# circuit_EDA.net
KiCad netlist of a schematic drawn in EasyEDA
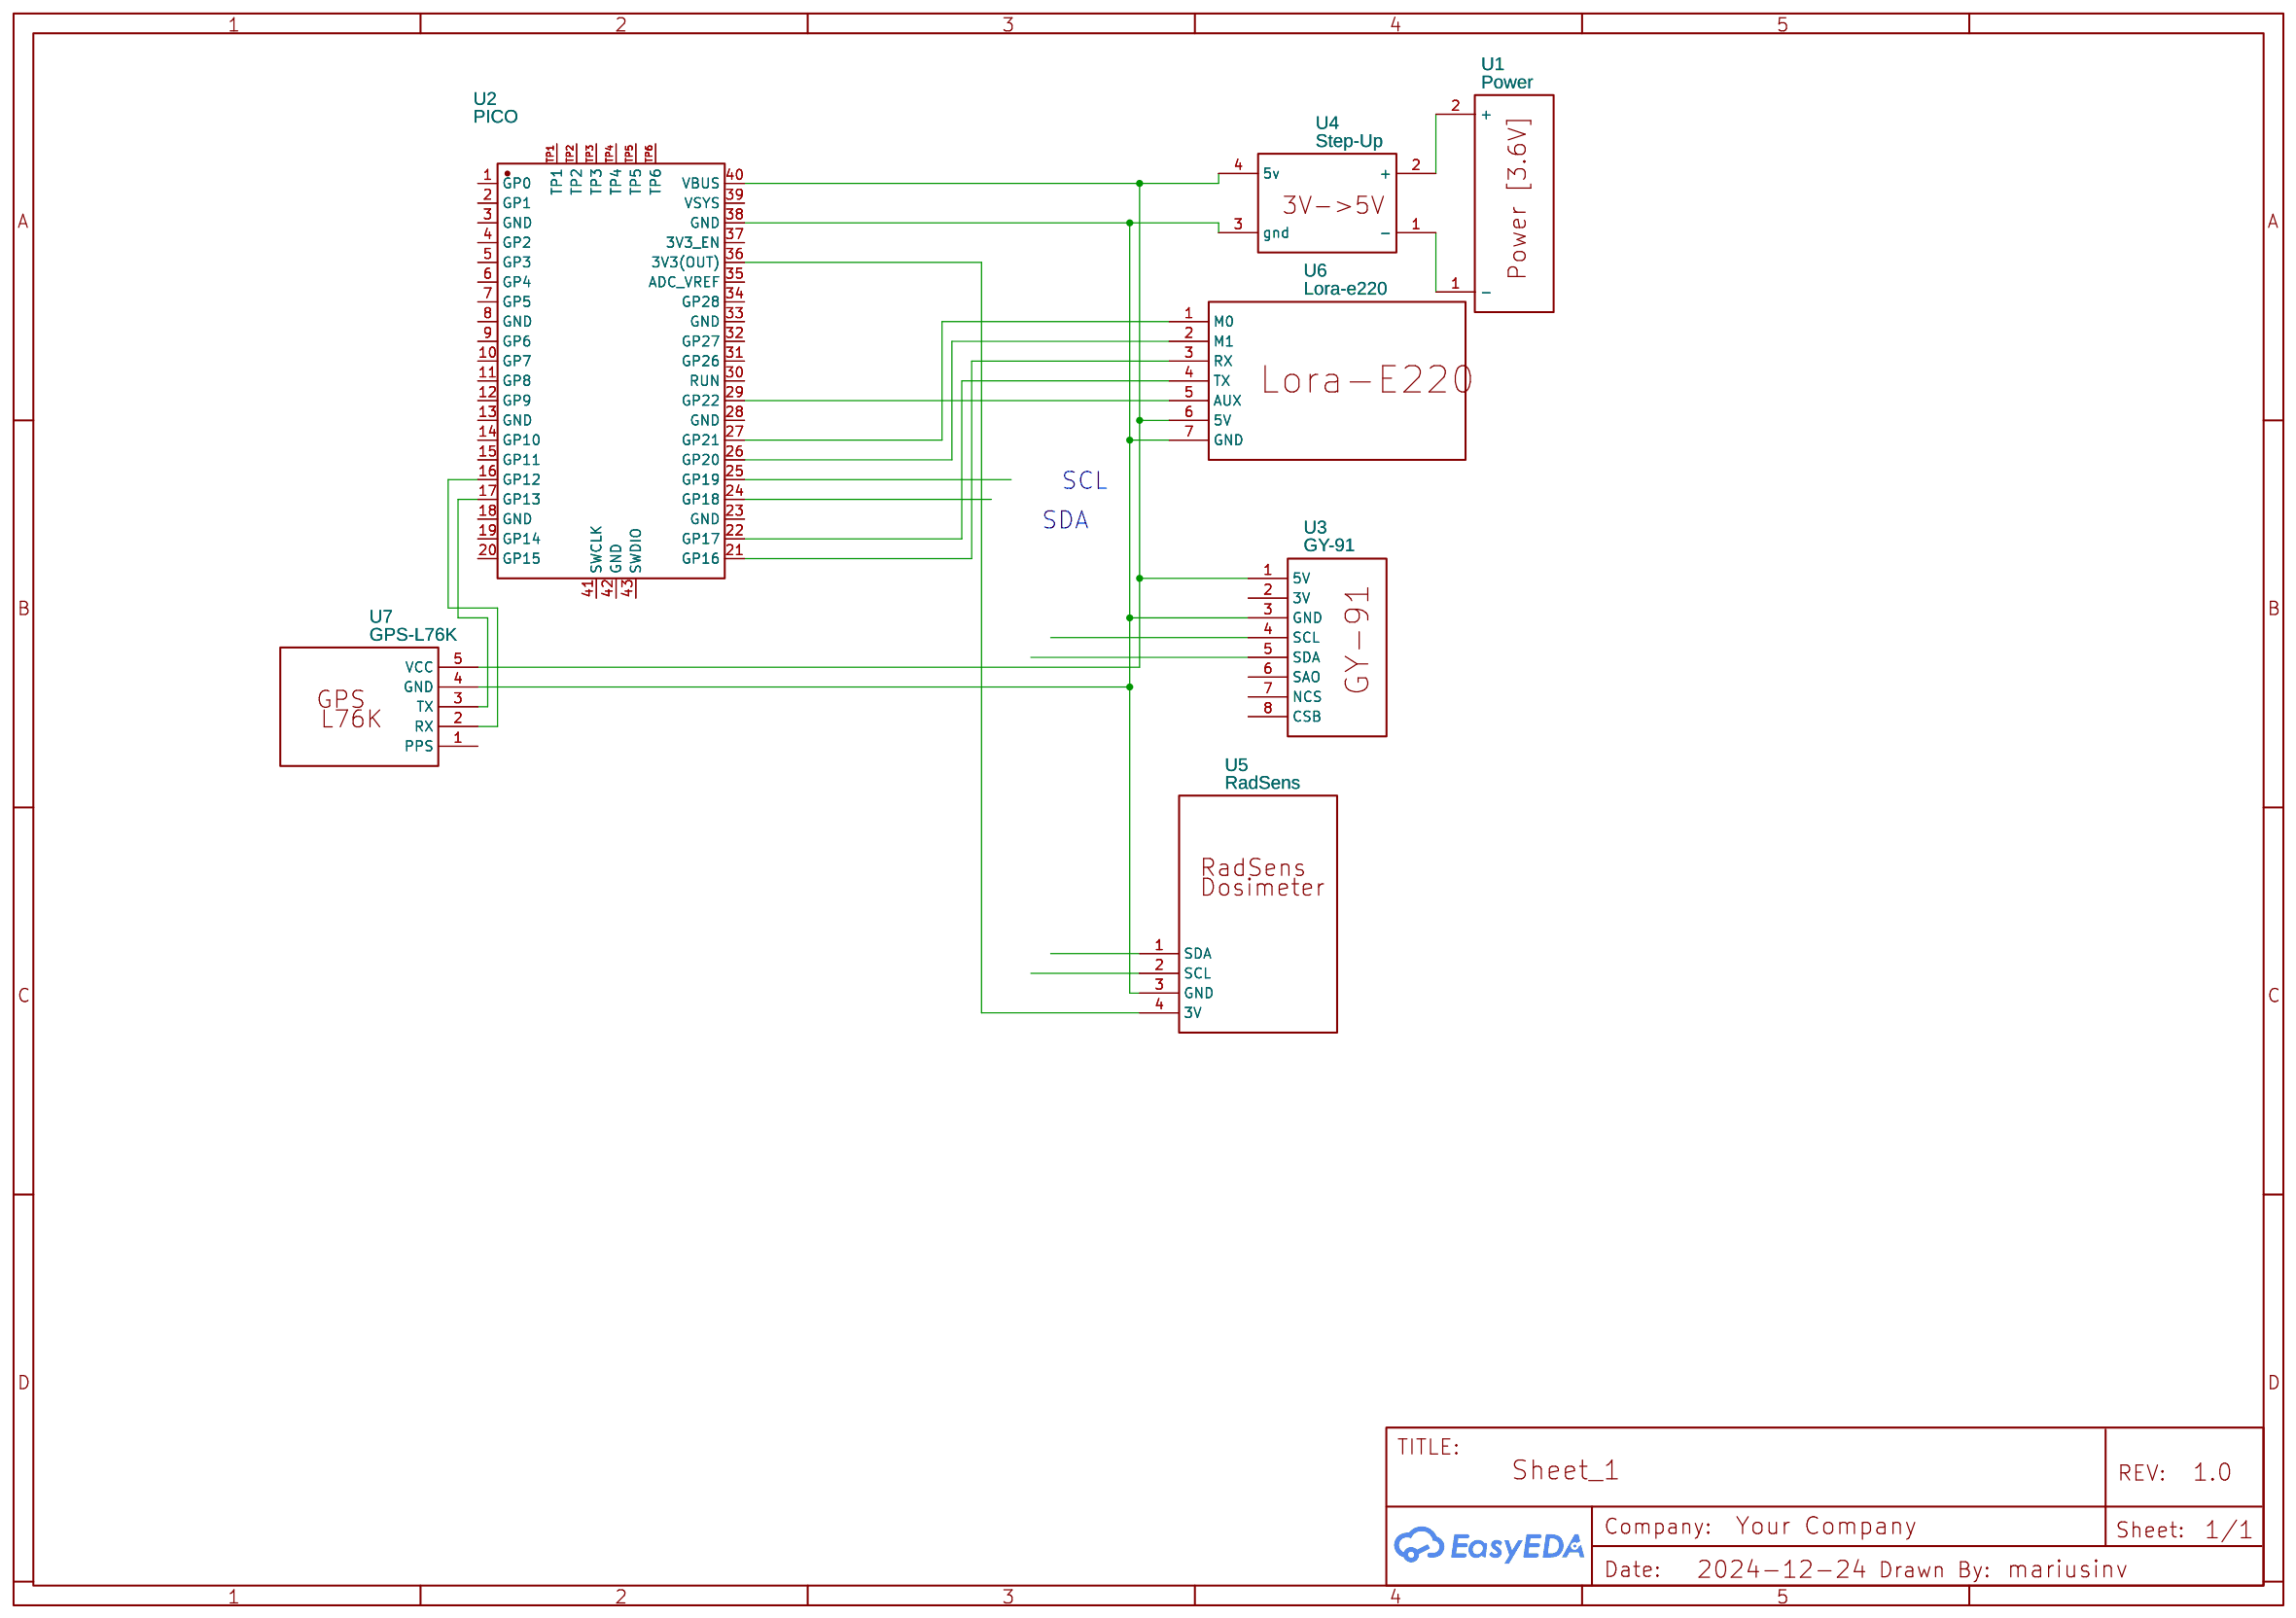
[diagram p0: schematic sheet]

(export (version "E")
  (design (tool "Eeschema 10.0.6"))
  (components
    (comp (ref "U1") (value "Power") (libsource (lib "") (part "Power")))
    (comp (ref "U2")
      (value "PICO")
      (fields (field (name "Manufacturer") "Raspberry Pi(树莓派)"))
      (libsource (lib "") (part "PICO"))
    )
    (comp (ref "U3") (value "GY-91") (libsource (lib "") (part "GY-91")))
    (comp (ref "U4") (value "Step-Up") (libsource (lib "") (part "Step-Up")))
    (comp (ref "U5") (value "RadSens") (libsource (lib "") (part "RadSens")))
    (comp (ref "U6") (value "Lora-e220") (libsource (lib "") (part "Lora-e220")))
    (comp (ref "U7") (value "GPS-L76K") (libsource (lib "") (part "GPS-L76K")))
  )
  (nets
    (net (code "1") (name "Net-(U1-+)") (class "Default")
      (node (ref "U1") (pin "2") (pinfunction "+_2") (pintype "unspecified"))
      (node (ref "U4") (pin "2") (pinfunction "+_2") (pintype "unspecified"))
    )
    (net (code "2") (name "Net-(U1--)") (class "Default")
      (node (ref "U1") (pin "1") (pinfunction "-_1") (pintype "unspecified"))
      (node (ref "U4") (pin "1") (pinfunction "-_1") (pintype "unspecified"))
    )
    (net (code "3") (name "Net-(U2-3V3(OUT))") (class "Default")
      (node (ref "U2") (pin "36") (pinfunction "3V3(OUT)_36") (pintype "unspecified"))
      (node (ref "U5") (pin "4") (pinfunction "3V_4") (pintype "unspecified"))
    )
    (net (code "4") (name "Net-(U2-GP12)") (class "Default")
      (node (ref "U2") (pin "16") (pinfunction "GP12_16") (pintype "unspecified"))
      (node (ref "U7") (pin "2") (pinfunction "RX_2") (pintype "unspecified"))
    )
    (net (code "5") (name "Net-(U2-GP13)") (class "Default")
      (node (ref "U2") (pin "17") (pinfunction "GP13_17") (pintype "unspecified"))
      (node (ref "U7") (pin "3") (pinfunction "TX_3") (pintype "unspecified"))
    )
    (net (code "6") (name "Net-(U2-GP16)") (class "Default")
      (node (ref "U2") (pin "21") (pinfunction "GP16_21") (pintype "unspecified"))
      (node (ref "U6") (pin "3") (pinfunction "RX_3") (pintype "unspecified"))
    )
    (net (code "7") (name "Net-(U2-GP17)") (class "Default")
      (node (ref "U2") (pin "22") (pinfunction "GP17_22") (pintype "unspecified"))
      (node (ref "U6") (pin "4") (pinfunction "TX_4") (pintype "unspecified"))
    )
    (net (code "8") (name "Net-(U2-GP20)") (class "Default")
      (node (ref "U2") (pin "26") (pinfunction "GP20_26") (pintype "unspecified"))
      (node (ref "U6") (pin "2") (pinfunction "M1_2") (pintype "unspecified"))
    )
    (net (code "9") (name "Net-(U2-GP21)") (class "Default")
      (node (ref "U2") (pin "27") (pinfunction "GP21_27") (pintype "unspecified"))
      (node (ref "U6") (pin "1") (pinfunction "M0_1") (pintype "unspecified"))
    )
    (net (code "10") (name "Net-(U2-GP22)") (class "Default")
      (node (ref "U2") (pin "29") (pinfunction "GP22_29") (pintype "unspecified"))
      (node (ref "U6") (pin "5") (pinfunction "AUX_5") (pintype "unspecified"))
    )
    (net (code "11") (name "Net-(U2-VBUS)") (class "Default")
      (node (ref "U2") (pin "40") (pinfunction "VBUS_40") (pintype "unspecified"))
      (node (ref "U3") (pin "1") (pinfunction "5V_1") (pintype "unspecified"))
      (node (ref "U4") (pin "4") (pinfunction "5v_4") (pintype "unspecified"))
      (node (ref "U6") (pin "6") (pinfunction "5V_6") (pintype "unspecified"))
      (node (ref "U7") (pin "5") (pinfunction "VCC_5") (pintype "unspecified"))
    )
    (net (code "12") (name "Net-(U3-GND)") (class "Default")
      (node (ref "U2") (pin "38") (pinfunction "GND_38") (pintype "unspecified"))
      (node (ref "U3") (pin "3") (pinfunction "GND_3") (pintype "unspecified"))
      (node (ref "U4") (pin "3") (pinfunction "gnd_3") (pintype "unspecified"))
      (node (ref "U5") (pin "3") (pinfunction "GND_3") (pintype "unspecified"))
      (node (ref "U6") (pin "7") (pinfunction "GND_7") (pintype "unspecified"))
      (node (ref "U7") (pin "4") (pinfunction "GND_4") (pintype "unspecified"))
    )
    (net (code "13") (name "unconnected-(U2-3V3_EN-Pad37)") (class "Default")
      (node (ref "U2") (pin "37") (pinfunction "3V3_EN_37") (pintype "unspecified"))
    )
    (net (code "14") (name "unconnected-(U2-ADC_VREF-Pad35)") (class "Default")
      (node (ref "U2") (pin "35") (pinfunction "ADC_VREF_35") (pintype "unspecified"))
    )
    (net (code "15") (name "unconnected-(U2-GND-Pad3)") (class "Default")
      (node (ref "U2") (pin "3") (pinfunction "GND_3") (pintype "unspecified"))
    )
    (net (code "16") (name "unconnected-(U2-GND-Pad8)") (class "Default")
      (node (ref "U2") (pin "8") (pinfunction "GND_8") (pintype "unspecified"))
    )
    (net (code "17") (name "unconnected-(U2-GND-Pad13)") (class "Default")
      (node (ref "U2") (pin "13") (pinfunction "GND_13") (pintype "unspecified"))
    )
    (net (code "18") (name "unconnected-(U2-GND-Pad18)") (class "Default")
      (node (ref "U2") (pin "18") (pinfunction "GND_18") (pintype "unspecified"))
    )
    (net (code "19") (name "unconnected-(U2-GND-Pad23)") (class "Default")
      (node (ref "U2") (pin "23") (pinfunction "GND_23") (pintype "unspecified"))
    )
    (net (code "20") (name "unconnected-(U2-GND-Pad28)") (class "Default")
      (node (ref "U2") (pin "28") (pinfunction "GND_28") (pintype "unspecified"))
    )
    (net (code "21") (name "unconnected-(U2-GND-Pad33)") (class "Default")
      (node (ref "U2") (pin "33") (pinfunction "GND_33") (pintype "unspecified"))
    )
    (net (code "22") (name "unconnected-(U2-GND-Pad42)") (class "Default")
      (node (ref "U2") (pin "42") (pinfunction "GND_42") (pintype "unspecified"))
    )
    (net (code "23") (name "unconnected-(U2-GP0-Pad1)") (class "Default")
      (node (ref "U2") (pin "1") (pinfunction "GP0_1") (pintype "unspecified"))
    )
    (net (code "24") (name "unconnected-(U2-GP1-Pad2)") (class "Default")
      (node (ref "U2") (pin "2") (pinfunction "GP1_2") (pintype "unspecified"))
    )
    (net (code "25") (name "unconnected-(U2-GP2-Pad4)") (class "Default")
      (node (ref "U2") (pin "4") (pinfunction "GP2_4") (pintype "unspecified"))
    )
    (net (code "26") (name "unconnected-(U2-GP3-Pad5)") (class "Default")
      (node (ref "U2") (pin "5") (pinfunction "GP3_5") (pintype "unspecified"))
    )
    (net (code "27") (name "unconnected-(U2-GP4-Pad6)") (class "Default")
      (node (ref "U2") (pin "6") (pinfunction "GP4_6") (pintype "unspecified"))
    )
    (net (code "28") (name "unconnected-(U2-GP5-Pad7)") (class "Default")
      (node (ref "U2") (pin "7") (pinfunction "GP5_7") (pintype "unspecified"))
    )
    (net (code "29") (name "unconnected-(U2-GP6-Pad9)") (class "Default")
      (node (ref "U2") (pin "9") (pinfunction "GP6_9") (pintype "unspecified"))
    )
    (net (code "30") (name "unconnected-(U2-GP7-Pad10)") (class "Default")
      (node (ref "U2") (pin "10") (pinfunction "GP7_10") (pintype "unspecified"))
    )
    (net (code "31") (name "unconnected-(U2-GP8-Pad11)") (class "Default")
      (node (ref "U2") (pin "11") (pinfunction "GP8_11") (pintype "unspecified"))
    )
    (net (code "32") (name "unconnected-(U2-GP9-Pad12)") (class "Default")
      (node (ref "U2") (pin "12") (pinfunction "GP9_12") (pintype "unspecified"))
    )
    (net (code "33") (name "unconnected-(U2-GP10-Pad14)") (class "Default")
      (node (ref "U2") (pin "14") (pinfunction "GP10_14") (pintype "unspecified"))
    )
    (net (code "34") (name "unconnected-(U2-GP11-Pad15)") (class "Default")
      (node (ref "U2") (pin "15") (pinfunction "GP11_15") (pintype "unspecified"))
    )
    (net (code "35") (name "unconnected-(U2-GP14-Pad19)") (class "Default")
      (node (ref "U2") (pin "19") (pinfunction "GP14_19") (pintype "unspecified"))
    )
    (net (code "36") (name "unconnected-(U2-GP15-Pad20)") (class "Default")
      (node (ref "U2") (pin "20") (pinfunction "GP15_20") (pintype "unspecified"))
    )
    (net (code "37") (name "unconnected-(U2-GP18-Pad24)") (class "Default")
      (node (ref "U2") (pin "24") (pinfunction "GP18_24") (pintype "unspecified"))
    )
    (net (code "38") (name "unconnected-(U2-GP19-Pad25)") (class "Default")
      (node (ref "U2") (pin "25") (pinfunction "GP19_25") (pintype "unspecified"))
    )
    (net (code "39") (name "unconnected-(U2-GP26-Pad31)") (class "Default")
      (node (ref "U2") (pin "31") (pinfunction "GP26_31") (pintype "unspecified"))
    )
    (net (code "40") (name "unconnected-(U2-GP27-Pad32)") (class "Default")
      (node (ref "U2") (pin "32") (pinfunction "GP27_32") (pintype "unspecified"))
    )
    (net (code "41") (name "unconnected-(U2-GP28-Pad34)") (class "Default")
      (node (ref "U2") (pin "34") (pinfunction "GP28_34") (pintype "unspecified"))
    )
    (net (code "42") (name "unconnected-(U2-PadTP1)") (class "Default")
      (node (ref "U2") (pin "TP1") (pinfunction "TP1_TP1") (pintype "unspecified"))
    )
    (net (code "43") (name "unconnected-(U2-PadTP2)") (class "Default")
      (node (ref "U2") (pin "TP2") (pinfunction "TP2_TP2") (pintype "unspecified"))
    )
    (net (code "44") (name "unconnected-(U2-PadTP3)") (class "Default")
      (node (ref "U2") (pin "TP3") (pinfunction "TP3_TP3") (pintype "unspecified"))
    )
    (net (code "45") (name "unconnected-(U2-PadTP4)") (class "Default")
      (node (ref "U2") (pin "TP4") (pinfunction "TP4_TP4") (pintype "unspecified"))
    )
    (net (code "46") (name "unconnected-(U2-PadTP5)") (class "Default")
      (node (ref "U2") (pin "TP5") (pinfunction "TP5_TP5") (pintype "unspecified"))
    )
    (net (code "47") (name "unconnected-(U2-PadTP6)") (class "Default")
      (node (ref "U2") (pin "TP6") (pinfunction "TP6_TP6") (pintype "unspecified"))
    )
    (net (code "48") (name "unconnected-(U2-RUN-Pad30)") (class "Default")
      (node (ref "U2") (pin "30") (pinfunction "RUN_30") (pintype "unspecified"))
    )
    (net (code "49") (name "unconnected-(U2-SWCLK-Pad41)") (class "Default")
      (node (ref "U2") (pin "41") (pinfunction "SWCLK_41") (pintype "unspecified"))
    )
    (net (code "50") (name "unconnected-(U2-SWDIO-Pad43)") (class "Default")
      (node (ref "U2") (pin "43") (pinfunction "SWDIO_43") (pintype "unspecified"))
    )
    (net (code "51") (name "unconnected-(U2-VSYS-Pad39)") (class "Default")
      (node (ref "U2") (pin "39") (pinfunction "VSYS_39") (pintype "unspecified"))
    )
    (net (code "52") (name "unconnected-(U3-3V-Pad2)") (class "Default")
      (node (ref "U3") (pin "2") (pinfunction "3V_2") (pintype "unspecified"))
    )
    (net (code "53") (name "unconnected-(U3-CSB-Pad8)") (class "Default")
      (node (ref "U3") (pin "8") (pinfunction "CSB_8") (pintype "unspecified"))
    )
    (net (code "54") (name "unconnected-(U3-NCS-Pad7)") (class "Default")
      (node (ref "U3") (pin "7") (pinfunction "NCS_7") (pintype "unspecified"))
    )
    (net (code "55") (name "unconnected-(U3-SAO-Pad6)") (class "Default")
      (node (ref "U3") (pin "6") (pinfunction "SAO_6") (pintype "unspecified"))
    )
    (net (code "56") (name "unconnected-(U3-SCL-Pad4)") (class "Default")
      (node (ref "U3") (pin "4") (pinfunction "SCL_4") (pintype "unspecified"))
    )
    (net (code "57") (name "unconnected-(U3-SDA-Pad5)") (class "Default")
      (node (ref "U3") (pin "5") (pinfunction "SDA_5") (pintype "unspecified"))
    )
    (net (code "58") (name "unconnected-(U5-SCL-Pad2)") (class "Default")
      (node (ref "U5") (pin "2") (pinfunction "SCL_2") (pintype "unspecified"))
    )
    (net (code "59") (name "unconnected-(U5-SDA-Pad1)") (class "Default")
      (node (ref "U5") (pin "1") (pinfunction "SDA_1") (pintype "unspecified"))
    )
    (net (code "60") (name "unconnected-(U7-PPS-Pad1)") (class "Default")
      (node (ref "U7") (pin "1") (pinfunction "PPS_1") (pintype "unspecified"))
    )
  )
)
